# 05_-_Gate_Drivers.net
KiCad netlist of a schematic drawn in Altium Designer
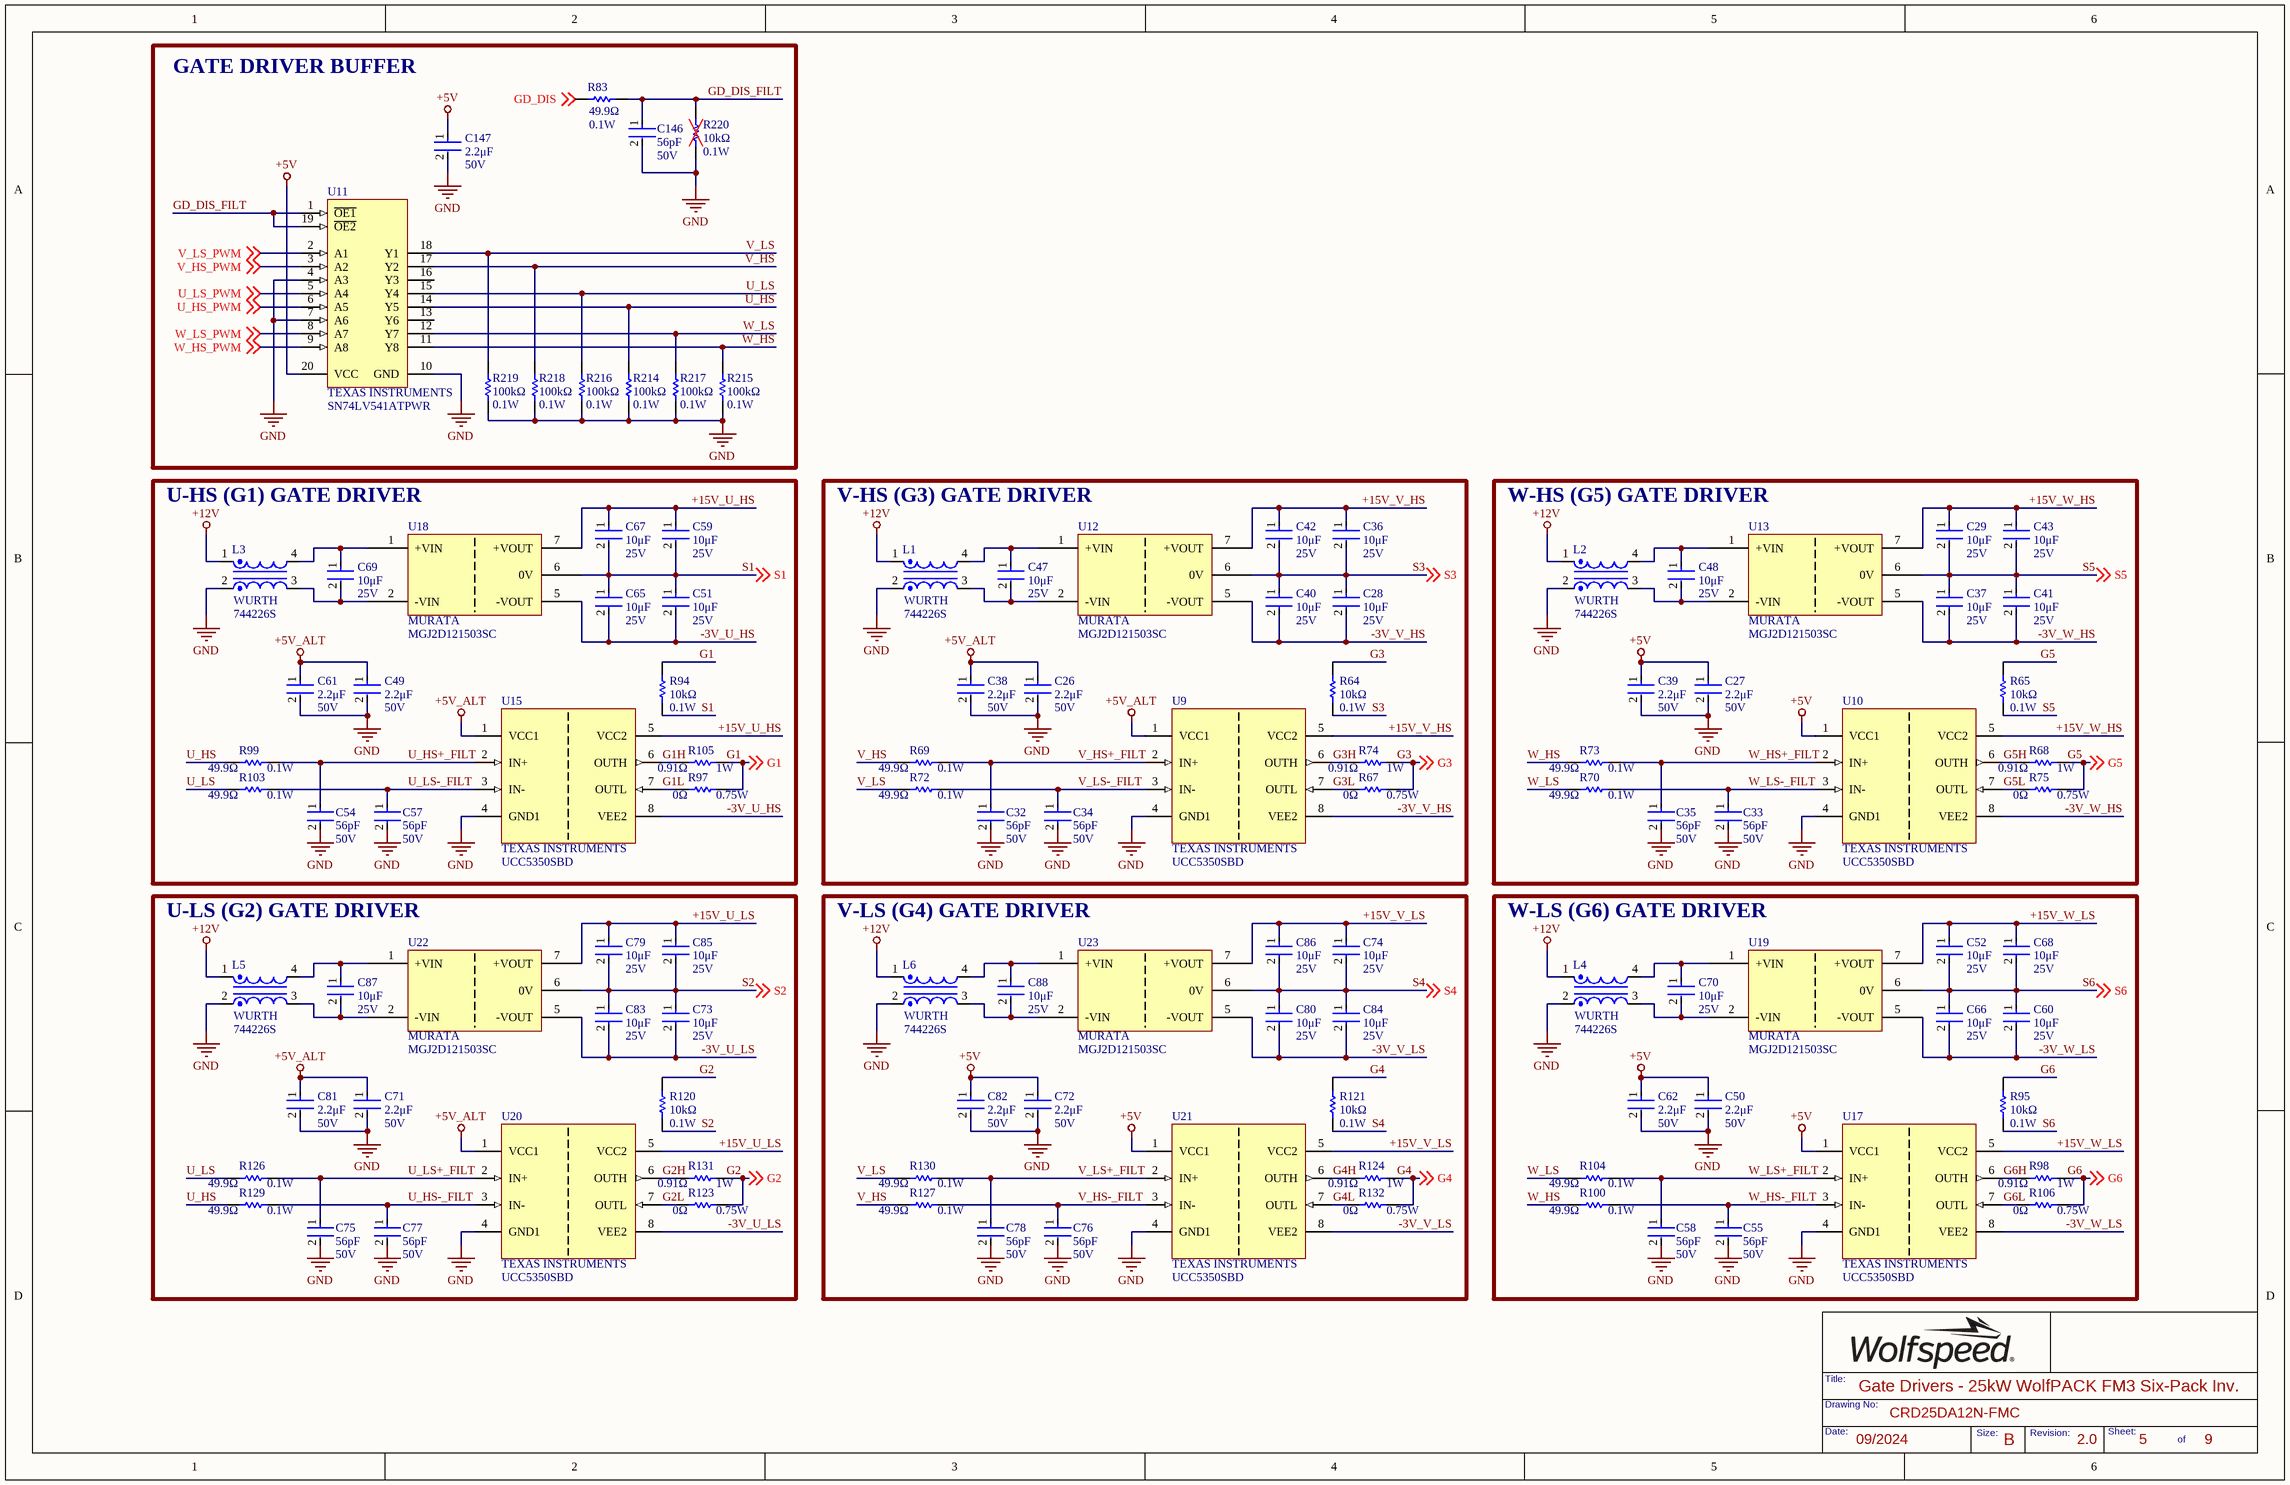
[diagram p0: 05 - Gate Drivers.SchDoc]

(export (version "E")
  (design (tool "Eeschema 10.0.6"))
  (components
    (comp (ref "C26")
      (value "GRT188R61H225ME13D")
      (footprint "FP-C0603C-CF-IPC_B")
      (description "CAP CER 2.2UF 50V X5R 0603")
      (fields
        (field (name "MANUFACTURER") "MURATA")
        (field (name "TOLERANCE") "20%")
        (field (name "VOLTAGE RATING") "50V")
        (field (name "CAPACITANCE") "2.2μF")
      )
      (libsource (lib "Inverter_25kW") (part "GRT188R61H225ME13D"))
    )
    (comp (ref "C27")
      (value "GRT188R61H225ME13D")
      (footprint "FP-C0603C-CF-IPC_B")
      (description "CAP CER 2.2UF 50V X5R 0603")
      (fields
        (field (name "MANUFACTURER") "MURATA")
        (field (name "TOLERANCE") "20%")
        (field (name "VOLTAGE RATING") "50V")
        (field (name "CAPACITANCE") "2.2μF")
      )
      (libsource (lib "Inverter_25kW") (part "GRT188R61H225ME13D"))
    )
    (comp (ref "C28")
      (value "CL31B106KAHSFNE")
      (footprint "FP-CL31-IPC_B")
      (description "CAP CER 10UF 25V X7R 1206")
      (fields
        (field (name "VOLTAGE RATING") "25V")
        (field (name "TOLERANCE") "10%")
        (field (name "CAPACITANCE") "10μF")
        (field (name "MANUFACTURER") "SAMSUNG")
      )
      (libsource (lib "Altium Content Vault") (part "b4654b650e69147ec39a6b967a45e02"))
    )
    (comp (ref "C29")
      (value "CL31B106KAHSFNE")
      (footprint "FP-CL31-IPC_B")
      (description "CAP CER 10UF 25V X7R 1206")
      (fields
        (field (name "VOLTAGE RATING") "25V")
        (field (name "TOLERANCE") "10%")
        (field (name "CAPACITANCE") "10μF")
        (field (name "MANUFACTURER") "SAMSUNG")
      )
      (libsource (lib "Altium Content Vault") (part "b4654b650e69147ec39a6b967a45e02"))
    )
    (comp (ref "C32")
      (value "CL10C560JB8NNNC")
      (footprint "FP-C0603C-CF-IPC_B")
      (description "CAP CER 56PF 50V C0G/NP0 0603")
      (fields
        (field (name "MANUFACTURER") "SAMSUNG")
        (field (name "TOLERANCE") "5%")
        (field (name "CAPACITANCE") "56pF")
        (field (name "VOLTAGE RATING") "50V")
      )
      (libsource (lib "Inverter_25kW") (part "CL10C560JB8NNNC"))
    )
    (comp (ref "C33")
      (value "CL10C560JB8NNNC")
      (footprint "FP-C0603C-CF-IPC_B")
      (description "CAP CER 56PF 50V C0G/NP0 0603")
      (fields
        (field (name "MANUFACTURER") "SAMSUNG")
        (field (name "TOLERANCE") "5%")
        (field (name "CAPACITANCE") "56pF")
        (field (name "VOLTAGE RATING") "50V")
      )
      (libsource (lib "Inverter_25kW") (part "CL10C560JB8NNNC"))
    )
    (comp (ref "C34")
      (value "CL10C560JB8NNNC")
      (footprint "FP-C0603C-CF-IPC_B")
      (description "CAP CER 56PF 50V C0G/NP0 0603")
      (fields
        (field (name "MANUFACTURER") "SAMSUNG")
        (field (name "TOLERANCE") "5%")
        (field (name "CAPACITANCE") "56pF")
        (field (name "VOLTAGE RATING") "50V")
      )
      (libsource (lib "Inverter_25kW") (part "CL10C560JB8NNNC"))
    )
    (comp (ref "C35")
      (value "CL10C560JB8NNNC")
      (footprint "FP-C0603C-CF-IPC_B")
      (description "CAP CER 56PF 50V C0G/NP0 0603")
      (fields
        (field (name "MANUFACTURER") "SAMSUNG")
        (field (name "TOLERANCE") "5%")
        (field (name "CAPACITANCE") "56pF")
        (field (name "VOLTAGE RATING") "50V")
      )
      (libsource (lib "Inverter_25kW") (part "CL10C560JB8NNNC"))
    )
    (comp (ref "C36")
      (value "CL31B106KAHSFNE")
      (footprint "FP-CL31-IPC_B")
      (description "CAP CER 10UF 25V X7R 1206")
      (fields
        (field (name "VOLTAGE RATING") "25V")
        (field (name "TOLERANCE") "10%")
        (field (name "CAPACITANCE") "10μF")
        (field (name "MANUFACTURER") "SAMSUNG")
      )
      (libsource (lib "Altium Content Vault") (part "b4654b650e69147ec39a6b967a45e02"))
    )
    (comp (ref "C37")
      (value "CL31B106KAHSFNE")
      (footprint "FP-CL31-IPC_B")
      (description "CAP CER 10UF 25V X7R 1206")
      (fields
        (field (name "VOLTAGE RATING") "25V")
        (field (name "TOLERANCE") "10%")
        (field (name "CAPACITANCE") "10μF")
        (field (name "MANUFACTURER") "SAMSUNG")
      )
      (libsource (lib "Altium Content Vault") (part "b4654b650e69147ec39a6b967a45e02"))
    )
    (comp (ref "C38")
      (value "GRT188R61H225ME13D")
      (footprint "FP-C0603C-CF-IPC_B")
      (description "CAP CER 2.2UF 50V X5R 0603")
      (fields
        (field (name "MANUFACTURER") "MURATA")
        (field (name "TOLERANCE") "20%")
        (field (name "VOLTAGE RATING") "50V")
        (field (name "CAPACITANCE") "2.2μF")
      )
      (libsource (lib "Inverter_25kW") (part "GRT188R61H225ME13D"))
    )
    (comp (ref "C39")
      (value "GRT188R61H225ME13D")
      (footprint "FP-C0603C-CF-IPC_B")
      (description "CAP CER 2.2UF 50V X5R 0603")
      (fields
        (field (name "MANUFACTURER") "MURATA")
        (field (name "TOLERANCE") "20%")
        (field (name "VOLTAGE RATING") "50V")
        (field (name "CAPACITANCE") "2.2μF")
      )
      (libsource (lib "Inverter_25kW") (part "GRT188R61H225ME13D"))
    )
    (comp (ref "C40")
      (value "CL31B106KAHSFNE")
      (footprint "FP-CL31-IPC_B")
      (description "CAP CER 10UF 25V X7R 1206")
      (fields
        (field (name "VOLTAGE RATING") "25V")
        (field (name "TOLERANCE") "10%")
        (field (name "CAPACITANCE") "10μF")
        (field (name "MANUFACTURER") "SAMSUNG")
      )
      (libsource (lib "Altium Content Vault") (part "b4654b650e69147ec39a6b967a45e02"))
    )
    (comp (ref "C41")
      (value "CL31B106KAHSFNE")
      (footprint "FP-CL31-IPC_B")
      (description "CAP CER 10UF 25V X7R 1206")
      (fields
        (field (name "VOLTAGE RATING") "25V")
        (field (name "TOLERANCE") "10%")
        (field (name "CAPACITANCE") "10μF")
        (field (name "MANUFACTURER") "SAMSUNG")
      )
      (libsource (lib "Altium Content Vault") (part "b4654b650e69147ec39a6b967a45e02"))
    )
    (comp (ref "C42")
      (value "CL31B106KAHSFNE")
      (footprint "FP-CL31-IPC_B")
      (description "CAP CER 10UF 25V X7R 1206")
      (fields
        (field (name "VOLTAGE RATING") "25V")
        (field (name "TOLERANCE") "10%")
        (field (name "CAPACITANCE") "10μF")
        (field (name "MANUFACTURER") "SAMSUNG")
      )
      (libsource (lib "Altium Content Vault") (part "b4654b650e69147ec39a6b967a45e02"))
    )
    (comp (ref "C43")
      (value "CL31B106KAHSFNE")
      (footprint "FP-CL31-IPC_B")
      (description "CAP CER 10UF 25V X7R 1206")
      (fields
        (field (name "VOLTAGE RATING") "25V")
        (field (name "TOLERANCE") "10%")
        (field (name "CAPACITANCE") "10μF")
        (field (name "MANUFACTURER") "SAMSUNG")
      )
      (libsource (lib "Altium Content Vault") (part "b4654b650e69147ec39a6b967a45e02"))
    )
    (comp (ref "C47")
      (value "CL31B106KAHSFNE")
      (footprint "FP-CL31-IPC_B")
      (description "CAP CER 10UF 25V X7R 1206")
      (fields
        (field (name "VOLTAGE RATING") "25V")
        (field (name "TOLERANCE") "10%")
        (field (name "CAPACITANCE") "10μF")
        (field (name "MANUFACTURER") "SAMSUNG")
      )
      (libsource (lib "Altium Content Vault") (part "b4654b650e69147ec39a6b967a45e02"))
    )
    (comp (ref "C48")
      (value "CL31B106KAHSFNE")
      (footprint "FP-CL31-IPC_B")
      (description "CAP CER 10UF 25V X7R 1206")
      (fields
        (field (name "VOLTAGE RATING") "25V")
        (field (name "TOLERANCE") "10%")
        (field (name "CAPACITANCE") "10μF")
        (field (name "MANUFACTURER") "SAMSUNG")
      )
      (libsource (lib "Altium Content Vault") (part "b4654b650e69147ec39a6b967a45e02"))
    )
    (comp (ref "C49")
      (value "GRT188R61H225ME13D")
      (footprint "FP-C0603C-CF-IPC_B")
      (description "CAP CER 2.2UF 50V X5R 0603")
      (fields
        (field (name "MANUFACTURER") "MURATA")
        (field (name "TOLERANCE") "20%")
        (field (name "VOLTAGE RATING") "50V")
        (field (name "CAPACITANCE") "2.2μF")
      )
      (libsource (lib "Inverter_25kW") (part "GRT188R61H225ME13D"))
    )
    (comp (ref "C50")
      (value "GRT188R61H225ME13D")
      (footprint "FP-C0603C-CF-IPC_B")
      (description "CAP CER 2.2UF 50V X5R 0603")
      (fields
        (field (name "MANUFACTURER") "MURATA")
        (field (name "TOLERANCE") "20%")
        (field (name "VOLTAGE RATING") "50V")
        (field (name "CAPACITANCE") "2.2μF")
      )
      (libsource (lib "Inverter_25kW") (part "GRT188R61H225ME13D"))
    )
    (comp (ref "C51")
      (value "CL31B106KAHSFNE")
      (footprint "FP-CL31-IPC_B")
      (description "CAP CER 10UF 25V X7R 1206")
      (fields
        (field (name "VOLTAGE RATING") "25V")
        (field (name "TOLERANCE") "10%")
        (field (name "CAPACITANCE") "10μF")
        (field (name "MANUFACTURER") "SAMSUNG")
      )
      (libsource (lib "Altium Content Vault") (part "b4654b650e69147ec39a6b967a45e02"))
    )
    (comp (ref "C52")
      (value "CL31B106KAHSFNE")
      (footprint "FP-CL31-IPC_B")
      (description "CAP CER 10UF 25V X7R 1206")
      (fields
        (field (name "VOLTAGE RATING") "25V")
        (field (name "TOLERANCE") "10%")
        (field (name "CAPACITANCE") "10μF")
        (field (name "MANUFACTURER") "SAMSUNG")
      )
      (libsource (lib "Altium Content Vault") (part "b4654b650e69147ec39a6b967a45e02"))
    )
    (comp (ref "C54")
      (value "CL10C560JB8NNNC")
      (footprint "FP-C0603C-CF-IPC_B")
      (description "CAP CER 56PF 50V C0G/NP0 0603")
      (fields
        (field (name "MANUFACTURER") "SAMSUNG")
        (field (name "TOLERANCE") "5%")
        (field (name "CAPACITANCE") "56pF")
        (field (name "VOLTAGE RATING") "50V")
      )
      (libsource (lib "Inverter_25kW") (part "CL10C560JB8NNNC"))
    )
    (comp (ref "C55")
      (value "CL10C560JB8NNNC")
      (footprint "FP-C0603C-CF-IPC_B")
      (description "CAP CER 56PF 50V C0G/NP0 0603")
      (fields
        (field (name "MANUFACTURER") "SAMSUNG")
        (field (name "TOLERANCE") "5%")
        (field (name "CAPACITANCE") "56pF")
        (field (name "VOLTAGE RATING") "50V")
      )
      (libsource (lib "Inverter_25kW") (part "CL10C560JB8NNNC"))
    )
    (comp (ref "C57")
      (value "CL10C560JB8NNNC")
      (footprint "FP-C0603C-CF-IPC_B")
      (description "CAP CER 56PF 50V C0G/NP0 0603")
      (fields
        (field (name "MANUFACTURER") "SAMSUNG")
        (field (name "TOLERANCE") "5%")
        (field (name "CAPACITANCE") "56pF")
        (field (name "VOLTAGE RATING") "50V")
      )
      (libsource (lib "Inverter_25kW") (part "CL10C560JB8NNNC"))
    )
    (comp (ref "C58")
      (value "CL10C560JB8NNNC")
      (footprint "FP-C0603C-CF-IPC_B")
      (description "CAP CER 56PF 50V C0G/NP0 0603")
      (fields
        (field (name "MANUFACTURER") "SAMSUNG")
        (field (name "TOLERANCE") "5%")
        (field (name "CAPACITANCE") "56pF")
        (field (name "VOLTAGE RATING") "50V")
      )
      (libsource (lib "Inverter_25kW") (part "CL10C560JB8NNNC"))
    )
    (comp (ref "C59")
      (value "CL31B106KAHSFNE")
      (footprint "FP-CL31-IPC_B")
      (description "CAP CER 10UF 25V X7R 1206")
      (fields
        (field (name "VOLTAGE RATING") "25V")
        (field (name "TOLERANCE") "10%")
        (field (name "CAPACITANCE") "10μF")
        (field (name "MANUFACTURER") "SAMSUNG")
      )
      (libsource (lib "Altium Content Vault") (part "b4654b650e69147ec39a6b967a45e02"))
    )
    (comp (ref "C60")
      (value "CL31B106KAHSFNE")
      (footprint "FP-CL31-IPC_B")
      (description "CAP CER 10UF 25V X7R 1206")
      (fields
        (field (name "VOLTAGE RATING") "25V")
        (field (name "TOLERANCE") "10%")
        (field (name "CAPACITANCE") "10μF")
        (field (name "MANUFACTURER") "SAMSUNG")
      )
      (libsource (lib "Altium Content Vault") (part "b4654b650e69147ec39a6b967a45e02"))
    )
    (comp (ref "C61")
      (value "GRT188R61H225ME13D")
      (footprint "FP-C0603C-CF-IPC_B")
      (description "CAP CER 2.2UF 50V X5R 0603")
      (fields
        (field (name "MANUFACTURER") "MURATA")
        (field (name "TOLERANCE") "20%")
        (field (name "VOLTAGE RATING") "50V")
        (field (name "CAPACITANCE") "2.2μF")
      )
      (libsource (lib "Inverter_25kW") (part "GRT188R61H225ME13D"))
    )
    (comp (ref "C62")
      (value "GRT188R61H225ME13D")
      (footprint "FP-C0603C-CF-IPC_B")
      (description "CAP CER 2.2UF 50V X5R 0603")
      (fields
        (field (name "MANUFACTURER") "MURATA")
        (field (name "TOLERANCE") "20%")
        (field (name "VOLTAGE RATING") "50V")
        (field (name "CAPACITANCE") "2.2μF")
      )
      (libsource (lib "Inverter_25kW") (part "GRT188R61H225ME13D"))
    )
    (comp (ref "C65")
      (value "CL31B106KAHSFNE")
      (footprint "FP-CL31-IPC_B")
      (description "CAP CER 10UF 25V X7R 1206")
      (fields
        (field (name "VOLTAGE RATING") "25V")
        (field (name "TOLERANCE") "10%")
        (field (name "CAPACITANCE") "10μF")
        (field (name "MANUFACTURER") "SAMSUNG")
      )
      (libsource (lib "Altium Content Vault") (part "b4654b650e69147ec39a6b967a45e02"))
    )
    (comp (ref "C66")
      (value "CL31B106KAHSFNE")
      (footprint "FP-CL31-IPC_B")
      (description "CAP CER 10UF 25V X7R 1206")
      (fields
        (field (name "VOLTAGE RATING") "25V")
        (field (name "TOLERANCE") "10%")
        (field (name "CAPACITANCE") "10μF")
        (field (name "MANUFACTURER") "SAMSUNG")
      )
      (libsource (lib "Altium Content Vault") (part "b4654b650e69147ec39a6b967a45e02"))
    )
    (comp (ref "C67")
      (value "CL31B106KAHSFNE")
      (footprint "FP-CL31-IPC_B")
      (description "CAP CER 10UF 25V X7R 1206")
      (fields
        (field (name "VOLTAGE RATING") "25V")
        (field (name "TOLERANCE") "10%")
        (field (name "CAPACITANCE") "10μF")
        (field (name "MANUFACTURER") "SAMSUNG")
      )
      (libsource (lib "Altium Content Vault") (part "b4654b650e69147ec39a6b967a45e02"))
    )
    (comp (ref "C68")
      (value "CL31B106KAHSFNE")
      (footprint "FP-CL31-IPC_B")
      (description "CAP CER 10UF 25V X7R 1206")
      (fields
        (field (name "VOLTAGE RATING") "25V")
        (field (name "TOLERANCE") "10%")
        (field (name "CAPACITANCE") "10μF")
        (field (name "MANUFACTURER") "SAMSUNG")
      )
      (libsource (lib "Altium Content Vault") (part "b4654b650e69147ec39a6b967a45e02"))
    )
    (comp (ref "C69")
      (value "CL31B106KAHSFNE")
      (footprint "FP-CL31-IPC_B")
      (description "CAP CER 10UF 25V X7R 1206")
      (fields
        (field (name "VOLTAGE RATING") "25V")
        (field (name "TOLERANCE") "10%")
        (field (name "CAPACITANCE") "10μF")
        (field (name "MANUFACTURER") "SAMSUNG")
      )
      (libsource (lib "Altium Content Vault") (part "b4654b650e69147ec39a6b967a45e02"))
    )
    (comp (ref "C70")
      (value "CL31B106KAHSFNE")
      (footprint "FP-CL31-IPC_B")
      (description "CAP CER 10UF 25V X7R 1206")
      (fields
        (field (name "VOLTAGE RATING") "25V")
        (field (name "TOLERANCE") "10%")
        (field (name "CAPACITANCE") "10μF")
        (field (name "MANUFACTURER") "SAMSUNG")
      )
      (libsource (lib "Altium Content Vault") (part "b4654b650e69147ec39a6b967a45e02"))
    )
    (comp (ref "C71")
      (value "GRT188R61H225ME13D")
      (footprint "FP-C0603C-CF-IPC_B")
      (description "CAP CER 2.2UF 50V X5R 0603")
      (fields
        (field (name "MANUFACTURER") "MURATA")
        (field (name "TOLERANCE") "20%")
        (field (name "VOLTAGE RATING") "50V")
        (field (name "CAPACITANCE") "2.2μF")
      )
      (libsource (lib "Inverter_25kW") (part "GRT188R61H225ME13D"))
    )
    (comp (ref "C72")
      (value "GRT188R61H225ME13D")
      (footprint "FP-C0603C-CF-IPC_B")
      (description "CAP CER 2.2UF 50V X5R 0603")
      (fields
        (field (name "MANUFACTURER") "MURATA")
        (field (name "TOLERANCE") "20%")
        (field (name "VOLTAGE RATING") "50V")
        (field (name "CAPACITANCE") "2.2μF")
      )
      (libsource (lib "Inverter_25kW") (part "GRT188R61H225ME13D"))
    )
    (comp (ref "C73")
      (value "CL31B106KAHSFNE")
      (footprint "FP-CL31-IPC_B")
      (description "CAP CER 10UF 25V X7R 1206")
      (fields
        (field (name "VOLTAGE RATING") "25V")
        (field (name "TOLERANCE") "10%")
        (field (name "CAPACITANCE") "10μF")
        (field (name "MANUFACTURER") "SAMSUNG")
      )
      (libsource (lib "Altium Content Vault") (part "b4654b650e69147ec39a6b967a45e02"))
    )
    (comp (ref "C74")
      (value "CL31B106KAHSFNE")
      (footprint "FP-CL31-IPC_B")
      (description "CAP CER 10UF 25V X7R 1206")
      (fields
        (field (name "VOLTAGE RATING") "25V")
        (field (name "TOLERANCE") "10%")
        (field (name "CAPACITANCE") "10μF")
        (field (name "MANUFACTURER") "SAMSUNG")
      )
      (libsource (lib "Altium Content Vault") (part "b4654b650e69147ec39a6b967a45e02"))
    )
    (comp (ref "C75")
      (value "CL10C560JB8NNNC")
      (footprint "FP-C0603C-CF-IPC_B")
      (description "CAP CER 56PF 50V C0G/NP0 0603")
      (fields
        (field (name "MANUFACTURER") "SAMSUNG")
        (field (name "TOLERANCE") "5%")
        (field (name "CAPACITANCE") "56pF")
        (field (name "VOLTAGE RATING") "50V")
      )
      (libsource (lib "Inverter_25kW") (part "CL10C560JB8NNNC"))
    )
    (comp (ref "C76")
      (value "CL10C560JB8NNNC")
      (footprint "FP-C0603C-CF-IPC_B")
      (description "CAP CER 56PF 50V C0G/NP0 0603")
      (fields
        (field (name "MANUFACTURER") "SAMSUNG")
        (field (name "TOLERANCE") "5%")
        (field (name "CAPACITANCE") "56pF")
        (field (name "VOLTAGE RATING") "50V")
      )
      (libsource (lib "Inverter_25kW") (part "CL10C560JB8NNNC"))
    )
    (comp (ref "C77")
      (value "CL10C560JB8NNNC")
      (footprint "FP-C0603C-CF-IPC_B")
      (description "CAP CER 56PF 50V C0G/NP0 0603")
      (fields
        (field (name "MANUFACTURER") "SAMSUNG")
        (field (name "TOLERANCE") "5%")
        (field (name "CAPACITANCE") "56pF")
        (field (name "VOLTAGE RATING") "50V")
      )
      (libsource (lib "Inverter_25kW") (part "CL10C560JB8NNNC"))
    )
    (comp (ref "C78")
      (value "CL10C560JB8NNNC")
      (footprint "FP-C0603C-CF-IPC_B")
      (description "CAP CER 56PF 50V C0G/NP0 0603")
      (fields
        (field (name "MANUFACTURER") "SAMSUNG")
        (field (name "TOLERANCE") "5%")
        (field (name "CAPACITANCE") "56pF")
        (field (name "VOLTAGE RATING") "50V")
      )
      (libsource (lib "Inverter_25kW") (part "CL10C560JB8NNNC"))
    )
    (comp (ref "C79")
      (value "CL31B106KAHSFNE")
      (footprint "FP-CL31-IPC_B")
      (description "CAP CER 10UF 25V X7R 1206")
      (fields
        (field (name "VOLTAGE RATING") "25V")
        (field (name "TOLERANCE") "10%")
        (field (name "CAPACITANCE") "10μF")
        (field (name "MANUFACTURER") "SAMSUNG")
      )
      (libsource (lib "Altium Content Vault") (part "b4654b650e69147ec39a6b967a45e02"))
    )
    (comp (ref "C80")
      (value "CL31B106KAHSFNE")
      (footprint "FP-CL31-IPC_B")
      (description "CAP CER 10UF 25V X7R 1206")
      (fields
        (field (name "VOLTAGE RATING") "25V")
        (field (name "TOLERANCE") "10%")
        (field (name "CAPACITANCE") "10μF")
        (field (name "MANUFACTURER") "SAMSUNG")
      )
      (libsource (lib "Altium Content Vault") (part "b4654b650e69147ec39a6b967a45e02"))
    )
    (comp (ref "C81")
      (value "GRT188R61H225ME13D")
      (footprint "FP-C0603C-CF-IPC_B")
      (description "CAP CER 2.2UF 50V X5R 0603")
      (fields
        (field (name "MANUFACTURER") "MURATA")
        (field (name "TOLERANCE") "20%")
        (field (name "VOLTAGE RATING") "50V")
        (field (name "CAPACITANCE") "2.2μF")
      )
      (libsource (lib "Inverter_25kW") (part "GRT188R61H225ME13D"))
    )
    (comp (ref "C82")
      (value "GRT188R61H225ME13D")
      (footprint "FP-C0603C-CF-IPC_B")
      (description "CAP CER 2.2UF 50V X5R 0603")
      (fields
        (field (name "MANUFACTURER") "MURATA")
        (field (name "TOLERANCE") "20%")
        (field (name "VOLTAGE RATING") "50V")
        (field (name "CAPACITANCE") "2.2μF")
      )
      (libsource (lib "Inverter_25kW") (part "GRT188R61H225ME13D"))
    )
    (comp (ref "C83")
      (value "CL31B106KAHSFNE")
      (footprint "FP-CL31-IPC_B")
      (description "CAP CER 10UF 25V X7R 1206")
      (fields
        (field (name "VOLTAGE RATING") "25V")
        (field (name "TOLERANCE") "10%")
        (field (name "CAPACITANCE") "10μF")
        (field (name "MANUFACTURER") "SAMSUNG")
      )
      (libsource (lib "Altium Content Vault") (part "b4654b650e69147ec39a6b967a45e02"))
    )
    (comp (ref "C84")
      (value "CL31B106KAHSFNE")
      (footprint "FP-CL31-IPC_B")
      (description "CAP CER 10UF 25V X7R 1206")
      (fields
        (field (name "VOLTAGE RATING") "25V")
        (field (name "TOLERANCE") "10%")
        (field (name "CAPACITANCE") "10μF")
        (field (name "MANUFACTURER") "SAMSUNG")
      )
      (libsource (lib "Altium Content Vault") (part "b4654b650e69147ec39a6b967a45e02"))
    )
    (comp (ref "C85")
      (value "CL31B106KAHSFNE")
      (footprint "FP-CL31-IPC_B")
      (description "CAP CER 10UF 25V X7R 1206")
      (fields
        (field (name "VOLTAGE RATING") "25V")
        (field (name "TOLERANCE") "10%")
        (field (name "CAPACITANCE") "10μF")
        (field (name "MANUFACTURER") "SAMSUNG")
      )
      (libsource (lib "Altium Content Vault") (part "b4654b650e69147ec39a6b967a45e02"))
    )
    (comp (ref "C86")
      (value "CL31B106KAHSFNE")
      (footprint "FP-CL31-IPC_B")
      (description "CAP CER 10UF 25V X7R 1206")
      (fields
        (field (name "VOLTAGE RATING") "25V")
        (field (name "TOLERANCE") "10%")
        (field (name "CAPACITANCE") "10μF")
        (field (name "MANUFACTURER") "SAMSUNG")
      )
      (libsource (lib "Altium Content Vault") (part "b4654b650e69147ec39a6b967a45e02"))
    )
    (comp (ref "C87")
      (value "CL31B106KAHSFNE")
      (footprint "FP-CL31-IPC_B")
      (description "CAP CER 10UF 25V X7R 1206")
      (fields
        (field (name "VOLTAGE RATING") "25V")
        (field (name "TOLERANCE") "10%")
        (field (name "CAPACITANCE") "10μF")
        (field (name "MANUFACTURER") "SAMSUNG")
      )
      (libsource (lib "Altium Content Vault") (part "b4654b650e69147ec39a6b967a45e02"))
    )
    (comp (ref "C88")
      (value "CL31B106KAHSFNE")
      (footprint "FP-CL31-IPC_B")
      (description "CAP CER 10UF 25V X7R 1206")
      (fields
        (field (name "VOLTAGE RATING") "25V")
        (field (name "TOLERANCE") "10%")
        (field (name "CAPACITANCE") "10μF")
        (field (name "MANUFACTURER") "SAMSUNG")
      )
      (libsource (lib "Altium Content Vault") (part "b4654b650e69147ec39a6b967a45e02"))
    )
    (comp (ref "C146")
      (value "CL10C560JB8NNNC")
      (footprint "FP-C0603C-CF-IPC_B")
      (description "CAP CER 56PF 50V C0G/NP0 0603")
      (fields
        (field (name "MANUFACTURER") "SAMSUNG")
        (field (name "TOLERANCE") "5%")
        (field (name "CAPACITANCE") "56pF")
        (field (name "VOLTAGE RATING") "50V")
      )
      (libsource (lib "Inverter_25kW") (part "CL10C560JB8NNNC"))
    )
    (comp (ref "C147")
      (value "GRT188R61H225ME13D")
      (footprint "FP-C0603C-CF-IPC_B")
      (description "CAP CER 2.2UF 50V X5R 0603")
      (fields
        (field (name "MANUFACTURER") "MURATA")
        (field (name "TOLERANCE") "20%")
        (field (name "VOLTAGE RATING") "50V")
        (field (name "CAPACITANCE") "2.2μF")
      )
      (libsource (lib "Inverter_25kW") (part "GRT188R61H225ME13D"))
    )
    (comp (ref "L1")
      (value "744226S")
      (footprint "Inverter_25kW:WE-SL2")
      (description "CMC 10UH 1.6A 2LN 920 OHM SMD")
      (fields
        (field (name "MANUFACTURER") "WURTH ELECTRONIK")
        (field (name "TOLERANCE") "30%")
        (field (name "MANUFACTURER PRINT") "WURTH")
      )
      (libsource (lib "Inverter_25kW") (part "744226S"))
    )
    (comp (ref "L2")
      (value "744226S")
      (footprint "Inverter_25kW:WE-SL2")
      (description "CMC 10UH 1.6A 2LN 920 OHM SMD")
      (fields
        (field (name "MANUFACTURER") "WURTH ELECTRONIK")
        (field (name "TOLERANCE") "30%")
        (field (name "MANUFACTURER PRINT") "WURTH")
      )
      (libsource (lib "Inverter_25kW") (part "744226S"))
    )
    (comp (ref "L3")
      (value "744226S")
      (footprint "Inverter_25kW:WE-SL2")
      (description "CMC 10UH 1.6A 2LN 920 OHM SMD")
      (fields
        (field (name "MANUFACTURER") "WURTH ELECTRONIK")
        (field (name "TOLERANCE") "30%")
        (field (name "MANUFACTURER PRINT") "WURTH")
      )
      (libsource (lib "Inverter_25kW") (part "744226S"))
    )
    (comp (ref "L4")
      (value "744226S")
      (footprint "Inverter_25kW:WE-SL2")
      (description "CMC 10UH 1.6A 2LN 920 OHM SMD")
      (fields
        (field (name "MANUFACTURER") "WURTH ELECTRONIK")
        (field (name "TOLERANCE") "30%")
        (field (name "MANUFACTURER PRINT") "WURTH")
      )
      (libsource (lib "Inverter_25kW") (part "744226S"))
    )
    (comp (ref "L5")
      (value "744226S")
      (footprint "Inverter_25kW:WE-SL2")
      (description "CMC 10UH 1.6A 2LN 920 OHM SMD")
      (fields
        (field (name "MANUFACTURER") "WURTH ELECTRONIK")
        (field (name "TOLERANCE") "30%")
        (field (name "MANUFACTURER PRINT") "WURTH")
      )
      (libsource (lib "Inverter_25kW") (part "744226S"))
    )
    (comp (ref "L6")
      (value "744226S")
      (footprint "Inverter_25kW:WE-SL2")
      (description "CMC 10UH 1.6A 2LN 920 OHM SMD")
      (fields
        (field (name "MANUFACTURER") "WURTH ELECTRONIK")
        (field (name "TOLERANCE") "30%")
        (field (name "MANUFACTURER PRINT") "WURTH")
      )
      (libsource (lib "Inverter_25kW") (part "744226S"))
    )
    (comp (ref "R64")
      (value "ERJ3EKF1002V")
      (footprint "FP-MCR03-IPC_B")
      (description "RES SMD 10K OHM 1% 1/10W 0603")
      (fields
        (field (name "MANUFACTURER") "PANASONIC")
        (field (name "MANUFACTURER PART NUMBER") "ERJ-3EKF1002V")
        (field (name "RESISTANCE") "10kΩ")
        (field (name "MAX POWER DISSIPATION") "0.1W")
      )
      (libsource (lib "Inverter_25kW") (part "ERJ3EKF1002V"))
    )
    (comp (ref "R65")
      (value "ERJ3EKF1002V")
      (footprint "FP-MCR03-IPC_B")
      (description "RES SMD 10K OHM 1% 1/10W 0603")
      (fields
        (field (name "MANUFACTURER") "PANASONIC")
        (field (name "MANUFACTURER PART NUMBER") "ERJ-3EKF1002V")
        (field (name "RESISTANCE") "10kΩ")
        (field (name "MAX POWER DISSIPATION") "0.1W")
      )
      (libsource (lib "Inverter_25kW") (part "ERJ3EKF1002V"))
    )
    (comp (ref "R67")
      (value "0Ω")
      (footprint "RESC3125X70X40NL20T20")
      (description "RES SMD 0 OHM JUMPER 3/4W 1210")
      (fields
        (field (name "MANUFACTURER") "VISHAY DALE")
        (field (name "MANUFACTURER PART NUMBER") "CRCW12100000Z0EAHP")
        (field (name "POWER RATING") "0.75W")
      )
      (libsource (lib "CRD25DA12N-FMC") (part "CRCW12100000Z0EAHP"))
    )
    (comp (ref "R68")
      (value "0.91Ω")
      (footprint "RESC3125X70X40NL20T20")
      (description "RES 0.91 OHM 1% 1W 1210")
      (fields
        (field (name "MANUFACTURER") "VISHAY DALE")
        (field (name "PART NUMBER") "RCWE1210R910FKEA")
        (field (name "POWER") "1W")
      )
      (libsource (lib "Altium Content Vault") (part "RES"))
    )
    (comp (ref "R69")
      (value "ERJ-3EKF49R9V")
      (footprint "FP-MCR03-IPC_B")
      (description "RES SMD 49.9 OHM 1% 1/10W 0603")
      (fields
        (field (name "MANUFACTURER") "PANASONIC")
        (field (name "TOLERANCE") "1%")
        (field (name "RESISTANCE") "49.9Ω")
        (field (name "POWER RATING") "0.1W")
      )
      (libsource (lib "Inverter_25kW") (part "ERJ-3EKF49R9V"))
    )
    (comp (ref "R70")
      (value "ERJ-3EKF49R9V")
      (footprint "FP-MCR03-IPC_B")
      (description "RES SMD 49.9 OHM 1% 1/10W 0603")
      (fields
        (field (name "MANUFACTURER") "PANASONIC")
        (field (name "TOLERANCE") "1%")
        (field (name "RESISTANCE") "49.9Ω")
        (field (name "POWER RATING") "0.1W")
      )
      (libsource (lib "Inverter_25kW") (part "ERJ-3EKF49R9V"))
    )
    (comp (ref "R72")
      (value "ERJ-3EKF49R9V")
      (footprint "FP-MCR03-IPC_B")
      (description "RES SMD 49.9 OHM 1% 1/10W 0603")
      (fields
        (field (name "MANUFACTURER") "PANASONIC")
        (field (name "TOLERANCE") "1%")
        (field (name "RESISTANCE") "49.9Ω")
        (field (name "POWER RATING") "0.1W")
      )
      (libsource (lib "Inverter_25kW") (part "ERJ-3EKF49R9V"))
    )
    (comp (ref "R73")
      (value "ERJ-3EKF49R9V")
      (footprint "FP-MCR03-IPC_B")
      (description "RES SMD 49.9 OHM 1% 1/10W 0603")
      (fields
        (field (name "MANUFACTURER") "PANASONIC")
        (field (name "TOLERANCE") "1%")
        (field (name "RESISTANCE") "49.9Ω")
        (field (name "POWER RATING") "0.1W")
      )
      (libsource (lib "Inverter_25kW") (part "ERJ-3EKF49R9V"))
    )
    (comp (ref "R74")
      (value "0.91Ω")
      (footprint "RESC3125X70X40NL20T20")
      (description "RES 0.91 OHM 1% 1W 1210")
      (fields
        (field (name "MANUFACTURER") "VISHAY DALE")
        (field (name "PART NUMBER") "RCWE1210R910FKEA")
        (field (name "POWER") "1W")
      )
      (libsource (lib "Altium Content Vault") (part "RES"))
    )
    (comp (ref "R75")
      (value "0Ω")
      (footprint "RESC3125X70X40NL20T20")
      (description "RES SMD 0 OHM JUMPER 3/4W 1210")
      (fields
        (field (name "MANUFACTURER") "VISHAY DALE")
        (field (name "MANUFACTURER PART NUMBER") "CRCW12100000Z0EAHP")
        (field (name "POWER RATING") "0.75W")
      )
      (libsource (lib "CRD25DA12N-FMC") (part "CRCW12100000Z0EAHP"))
    )
    (comp (ref "R83")
      (value "ERJ-3EKF49R9V")
      (footprint "FP-MCR03-IPC_B")
      (description "RES SMD 49.9 OHM 1% 1/10W 0603")
      (fields
        (field (name "MANUFACTURER") "PANASONIC")
        (field (name "TOLERANCE") "1%")
        (field (name "RESISTANCE") "49.9Ω")
        (field (name "POWER RATING") "0.1W")
      )
      (libsource (lib "Inverter_25kW") (part "ERJ-3EKF49R9V"))
    )
    (comp (ref "R94")
      (value "ERJ3EKF1002V")
      (footprint "FP-MCR03-IPC_B")
      (description "RES SMD 10K OHM 1% 1/10W 0603")
      (fields
        (field (name "MANUFACTURER") "PANASONIC")
        (field (name "MANUFACTURER PART NUMBER") "ERJ-3EKF1002V")
        (field (name "RESISTANCE") "10kΩ")
        (field (name "MAX POWER DISSIPATION") "0.1W")
      )
      (libsource (lib "Inverter_25kW") (part "ERJ3EKF1002V"))
    )
    (comp (ref "R95")
      (value "ERJ3EKF1002V")
      (footprint "FP-MCR03-IPC_B")
      (description "RES SMD 10K OHM 1% 1/10W 0603")
      (fields
        (field (name "MANUFACTURER") "PANASONIC")
        (field (name "MANUFACTURER PART NUMBER") "ERJ-3EKF1002V")
        (field (name "RESISTANCE") "10kΩ")
        (field (name "MAX POWER DISSIPATION") "0.1W")
      )
      (libsource (lib "Inverter_25kW") (part "ERJ3EKF1002V"))
    )
    (comp (ref "R97")
      (value "0Ω")
      (footprint "RESC3125X70X40NL20T20")
      (description "RES SMD 0 OHM JUMPER 3/4W 1210")
      (fields
        (field (name "MANUFACTURER") "VISHAY DALE")
        (field (name "MANUFACTURER PART NUMBER") "CRCW12100000Z0EAHP")
        (field (name "POWER RATING") "0.75W")
      )
      (libsource (lib "CRD25DA12N-FMC") (part "CRCW12100000Z0EAHP"))
    )
    (comp (ref "R98")
      (value "0.91Ω")
      (footprint "RESC3125X70X40NL20T20")
      (description "RES 0.91 OHM 1% 1W 1210")
      (fields
        (field (name "MANUFACTURER") "VISHAY DALE")
        (field (name "PART NUMBER") "RCWE1210R910FKEA")
        (field (name "POWER") "1W")
      )
      (libsource (lib "Altium Content Vault") (part "RES"))
    )
    (comp (ref "R99")
      (value "ERJ-3EKF49R9V")
      (footprint "FP-MCR03-IPC_B")
      (description "RES SMD 49.9 OHM 1% 1/10W 0603")
      (fields
        (field (name "MANUFACTURER") "PANASONIC")
        (field (name "TOLERANCE") "1%")
        (field (name "RESISTANCE") "49.9Ω")
        (field (name "POWER RATING") "0.1W")
      )
      (libsource (lib "Inverter_25kW") (part "ERJ-3EKF49R9V"))
    )
    (comp (ref "R100")
      (value "ERJ-3EKF49R9V")
      (footprint "FP-MCR03-IPC_B")
      (description "RES SMD 49.9 OHM 1% 1/10W 0603")
      (fields
        (field (name "MANUFACTURER") "PANASONIC")
        (field (name "TOLERANCE") "1%")
        (field (name "RESISTANCE") "49.9Ω")
        (field (name "POWER RATING") "0.1W")
      )
      (libsource (lib "Inverter_25kW") (part "ERJ-3EKF49R9V"))
    )
    (comp (ref "R103")
      (value "ERJ-3EKF49R9V")
      (footprint "FP-MCR03-IPC_B")
      (description "RES SMD 49.9 OHM 1% 1/10W 0603")
      (fields
        (field (name "MANUFACTURER") "PANASONIC")
        (field (name "TOLERANCE") "1%")
        (field (name "RESISTANCE") "49.9Ω")
        (field (name "POWER RATING") "0.1W")
      )
      (libsource (lib "Inverter_25kW") (part "ERJ-3EKF49R9V"))
    )
    (comp (ref "R104")
      (value "ERJ-3EKF49R9V")
      (footprint "FP-MCR03-IPC_B")
      (description "RES SMD 49.9 OHM 1% 1/10W 0603")
      (fields
        (field (name "MANUFACTURER") "PANASONIC")
        (field (name "TOLERANCE") "1%")
        (field (name "RESISTANCE") "49.9Ω")
        (field (name "POWER RATING") "0.1W")
      )
      (libsource (lib "Inverter_25kW") (part "ERJ-3EKF49R9V"))
    )
    (comp (ref "R105")
      (value "0.91Ω")
      (footprint "RESC3125X70X40NL20T20")
      (description "RES 0.91 OHM 1% 1W 1210")
      (fields
        (field (name "MANUFACTURER") "VISHAY DALE")
        (field (name "PART NUMBER") "RCWE1210R910FKEA")
        (field (name "POWER") "1W")
      )
      (libsource (lib "Altium Content Vault") (part "RES"))
    )
    (comp (ref "R106")
      (value "0Ω")
      (footprint "RESC3125X70X40NL20T20")
      (description "RES SMD 0 OHM JUMPER 3/4W 1210")
      (fields
        (field (name "MANUFACTURER") "VISHAY DALE")
        (field (name "MANUFACTURER PART NUMBER") "CRCW12100000Z0EAHP")
        (field (name "POWER RATING") "0.75W")
      )
      (libsource (lib "CRD25DA12N-FMC") (part "CRCW12100000Z0EAHP"))
    )
    (comp (ref "R120")
      (value "ERJ3EKF1002V")
      (footprint "FP-MCR03-IPC_B")
      (description "RES SMD 10K OHM 1% 1/10W 0603")
      (fields
        (field (name "MANUFACTURER") "PANASONIC")
        (field (name "MANUFACTURER PART NUMBER") "ERJ-3EKF1002V")
        (field (name "RESISTANCE") "10kΩ")
        (field (name "MAX POWER DISSIPATION") "0.1W")
      )
      (libsource (lib "Inverter_25kW") (part "ERJ3EKF1002V"))
    )
    (comp (ref "R121")
      (value "ERJ3EKF1002V")
      (footprint "FP-MCR03-IPC_B")
      (description "RES SMD 10K OHM 1% 1/10W 0603")
      (fields
        (field (name "MANUFACTURER") "PANASONIC")
        (field (name "MANUFACTURER PART NUMBER") "ERJ-3EKF1002V")
        (field (name "RESISTANCE") "10kΩ")
        (field (name "MAX POWER DISSIPATION") "0.1W")
      )
      (libsource (lib "Inverter_25kW") (part "ERJ3EKF1002V"))
    )
    (comp (ref "R123")
      (value "0Ω")
      (footprint "RESC3125X70X40NL20T20")
      (description "RES SMD 0 OHM JUMPER 3/4W 1210")
      (fields
        (field (name "MANUFACTURER") "VISHAY DALE")
        (field (name "MANUFACTURER PART NUMBER") "CRCW12100000Z0EAHP")
        (field (name "POWER RATING") "0.75W")
      )
      (libsource (lib "CRD25DA12N-FMC") (part "CRCW12100000Z0EAHP"))
    )
    (comp (ref "R124")
      (value "0.91Ω")
      (footprint "RESC3125X70X40NL20T20")
      (description "RES 0.91 OHM 1% 1W 1210")
      (fields
        (field (name "MANUFACTURER") "VISHAY DALE")
        (field (name "PART NUMBER") "RCWE1210R910FKEA")
        (field (name "POWER") "1W")
      )
      (libsource (lib "Altium Content Vault") (part "RES"))
    )
    (comp (ref "R126")
      (value "ERJ-3EKF49R9V")
      (footprint "FP-MCR03-IPC_B")
      (description "RES SMD 49.9 OHM 1% 1/10W 0603")
      (fields
        (field (name "MANUFACTURER") "PANASONIC")
        (field (name "TOLERANCE") "1%")
        (field (name "RESISTANCE") "49.9Ω")
        (field (name "POWER RATING") "0.1W")
      )
      (libsource (lib "Inverter_25kW") (part "ERJ-3EKF49R9V"))
    )
    (comp (ref "R127")
      (value "ERJ-3EKF49R9V")
      (footprint "FP-MCR03-IPC_B")
      (description "RES SMD 49.9 OHM 1% 1/10W 0603")
      (fields
        (field (name "MANUFACTURER") "PANASONIC")
        (field (name "TOLERANCE") "1%")
        (field (name "RESISTANCE") "49.9Ω")
        (field (name "POWER RATING") "0.1W")
      )
      (libsource (lib "Inverter_25kW") (part "ERJ-3EKF49R9V"))
    )
    (comp (ref "R129")
      (value "ERJ-3EKF49R9V")
      (footprint "FP-MCR03-IPC_B")
      (description "RES SMD 49.9 OHM 1% 1/10W 0603")
      (fields
        (field (name "MANUFACTURER") "PANASONIC")
        (field (name "TOLERANCE") "1%")
        (field (name "RESISTANCE") "49.9Ω")
        (field (name "POWER RATING") "0.1W")
      )
      (libsource (lib "Inverter_25kW") (part "ERJ-3EKF49R9V"))
    )
    (comp (ref "R130")
      (value "ERJ-3EKF49R9V")
      (footprint "FP-MCR03-IPC_B")
      (description "RES SMD 49.9 OHM 1% 1/10W 0603")
      (fields
        (field (name "MANUFACTURER") "PANASONIC")
        (field (name "TOLERANCE") "1%")
        (field (name "RESISTANCE") "49.9Ω")
        (field (name "POWER RATING") "0.1W")
      )
      (libsource (lib "Inverter_25kW") (part "ERJ-3EKF49R9V"))
    )
    (comp (ref "R131")
      (value "0.91Ω")
      (footprint "RESC3125X70X40NL20T20")
      (description "RES 0.91 OHM 1% 1W 1210")
      (fields
        (field (name "MANUFACTURER") "VISHAY DALE")
        (field (name "PART NUMBER") "RCWE1210R910FKEA")
        (field (name "POWER") "1W")
      )
      (libsource (lib "Altium Content Vault") (part "RES"))
    )
    (comp (ref "R132")
      (value "0Ω")
      (footprint "RESC3125X70X40NL20T20")
      (description "RES SMD 0 OHM JUMPER 3/4W 1210")
      (fields
        (field (name "MANUFACTURER") "VISHAY DALE")
        (field (name "MANUFACTURER PART NUMBER") "CRCW12100000Z0EAHP")
        (field (name "POWER RATING") "0.75W")
      )
      (libsource (lib "CRD25DA12N-FMC") (part "CRCW12100000Z0EAHP"))
    )
    (comp (ref "R214")
      (value "RC0603FR-07100KL")
      (footprint "FP-MCR03-IPC_B")
      (description "RES 100K OHM 1% 1/10W 0603")
      (fields
        (field (name "MANUFACTURER") "YAGEO")
        (field (name "TOLERANCE") "1%")
        (field (name "RESISTANCE") "100kΩ")
        (field (name "POWER RATING") "0.1W")
      )
      (libsource (lib "Inverter_25kW") (part "RC0603FR-07100KL"))
    )
    (comp (ref "R215")
      (value "RC0603FR-07100KL")
      (footprint "FP-MCR03-IPC_B")
      (description "RES 100K OHM 1% 1/10W 0603")
      (fields
        (field (name "MANUFACTURER") "YAGEO")
        (field (name "TOLERANCE") "1%")
        (field (name "RESISTANCE") "100kΩ")
        (field (name "POWER RATING") "0.1W")
      )
      (libsource (lib "Inverter_25kW") (part "RC0603FR-07100KL"))
    )
    (comp (ref "R216")
      (value "RC0603FR-07100KL")
      (footprint "FP-MCR03-IPC_B")
      (description "RES 100K OHM 1% 1/10W 0603")
      (fields
        (field (name "MANUFACTURER") "YAGEO")
        (field (name "TOLERANCE") "1%")
        (field (name "RESISTANCE") "100kΩ")
        (field (name "POWER RATING") "0.1W")
      )
      (libsource (lib "Inverter_25kW") (part "RC0603FR-07100KL"))
    )
    (comp (ref "R217")
      (value "RC0603FR-07100KL")
      (footprint "FP-MCR03-IPC_B")
      (description "RES 100K OHM 1% 1/10W 0603")
      (fields
        (field (name "MANUFACTURER") "YAGEO")
        (field (name "TOLERANCE") "1%")
        (field (name "RESISTANCE") "100kΩ")
        (field (name "POWER RATING") "0.1W")
      )
      (libsource (lib "Inverter_25kW") (part "RC0603FR-07100KL"))
    )
    (comp (ref "R218")
      (value "RC0603FR-07100KL")
      (footprint "FP-MCR03-IPC_B")
      (description "RES 100K OHM 1% 1/10W 0603")
      (fields
        (field (name "MANUFACTURER") "YAGEO")
        (field (name "TOLERANCE") "1%")
        (field (name "RESISTANCE") "100kΩ")
        (field (name "POWER RATING") "0.1W")
      )
      (libsource (lib "Inverter_25kW") (part "RC0603FR-07100KL"))
    )
    (comp (ref "R219")
      (value "RC0603FR-07100KL")
      (footprint "FP-MCR03-IPC_B")
      (description "RES 100K OHM 1% 1/10W 0603")
      (fields
        (field (name "MANUFACTURER") "YAGEO")
        (field (name "TOLERANCE") "1%")
        (field (name "RESISTANCE") "100kΩ")
        (field (name "POWER RATING") "0.1W")
      )
      (libsource (lib "Inverter_25kW") (part "RC0603FR-07100KL"))
    )
    (comp (ref "R220")
      (value "ERJ3EKF1002V")
      (footprint "FP-MCR03-IPC_B")
      (description "RES SMD 10K OHM 1% 1/10W 0603")
      (fields
        (field (name "MANUFACTURER") "PANASONIC")
        (field (name "MANUFACTURER PART NUMBER") "ERJ-3EKF1002V")
        (field (name "RESISTANCE") "10kΩ")
        (field (name "MAX POWER DISSIPATION") "0.1W")
      )
      (libsource (lib "Inverter_25kW") (part "ERJ3EKF1002V"))
    )
    (comp (ref "U9")
      (value "UCC5350SBD")
      (footprint "D0008B_HV")
      (description "5A/5A, 3-KVRMS SINGLE-CHANNEL IS")
      (fields
        (field (name "MANUFACTURER") "TEXAS INSTRUMENTS")
        (field (name "MANUFACTURER PRINT") "TEXAS INSTRUMENTS")
        (field (name "COPYRIGHT") "Copyright (C) 2021 Ultra Librarian. All rights reserved.")
      )
      (libsource (lib "Inverter_25kW") (part "UCC5350SBD"))
    )
    (comp (ref "U10")
      (value "UCC5350SBD")
      (footprint "D0008B_HV")
      (description "5A/5A, 3-KVRMS SINGLE-CHANNEL IS")
      (fields
        (field (name "MANUFACTURER") "TEXAS INSTRUMENTS")
        (field (name "MANUFACTURER PRINT") "TEXAS INSTRUMENTS")
        (field (name "COPYRIGHT") "Copyright (C) 2021 Ultra Librarian. All rights reserved.")
      )
      (libsource (lib "Inverter_25kW") (part "UCC5350SBD"))
    )
    (comp (ref "U11")
      (value "SN74LV541ATPWR")
      (footprint "PW0020A_L")
      (description "IC BUF NON-INVERT 5.5V 20TSSOP")
      (fields
        (field (name "GENERIC PART NUMBER") "SN74LV541AT")
        (field (name "MANUFACTURER") "TEXAS INSTRUMENTS")
        (field (name "MANUFACTURER PART NUMBER") "SN74LV541ATPWR")
      )
      (libsource (lib "Altium Content Vault") (part "TI-SN54_74_CD74XXXX541XX-20"))
    )
    (comp (ref "U12")
      (value "MGJ2D121503SC")
      (footprint "Inverter_25kW:MGJ2D121509SC")
      (description "DC DC CONVERTER 15V -3V 1.7W")
      (fields (field (name "MANUFACTURER") "MURATA") (field (name "MANUFACTURER PRINT") "MURATA"))
      (libsource (lib "Inverter_25kW") (part "MGJ2D121503SC"))
    )
    (comp (ref "U13")
      (value "MGJ2D121503SC")
      (footprint "Inverter_25kW:MGJ2D121509SC")
      (description "DC DC CONVERTER 15V -3V 1.7W")
      (fields (field (name "MANUFACTURER") "MURATA") (field (name "MANUFACTURER PRINT") "MURATA"))
      (libsource (lib "Inverter_25kW") (part "MGJ2D121503SC"))
    )
    (comp (ref "U15")
      (value "UCC5350SBD")
      (footprint "D0008B_HV")
      (description "5A/5A, 3-KVRMS SINGLE-CHANNEL IS")
      (fields
        (field (name "MANUFACTURER") "TEXAS INSTRUMENTS")
        (field (name "MANUFACTURER PRINT") "TEXAS INSTRUMENTS")
        (field (name "COPYRIGHT") "Copyright (C) 2021 Ultra Librarian. All rights reserved.")
      )
      (libsource (lib "Inverter_25kW") (part "UCC5350SBD"))
    )
    (comp (ref "U17")
      (value "UCC5350SBD")
      (footprint "D0008B_HV")
      (description "5A/5A, 3-KVRMS SINGLE-CHANNEL IS")
      (fields
        (field (name "MANUFACTURER") "TEXAS INSTRUMENTS")
        (field (name "MANUFACTURER PRINT") "TEXAS INSTRUMENTS")
        (field (name "COPYRIGHT") "Copyright (C) 2021 Ultra Librarian. All rights reserved.")
      )
      (libsource (lib "Inverter_25kW") (part "UCC5350SBD"))
    )
    (comp (ref "U18")
      (value "MGJ2D121503SC")
      (footprint "Inverter_25kW:MGJ2D121509SC")
      (description "DC DC CONVERTER 15V -3V 1.7W")
      (fields (field (name "MANUFACTURER") "MURATA") (field (name "MANUFACTURER PRINT") "MURATA"))
      (libsource (lib "Inverter_25kW") (part "MGJ2D121503SC"))
    )
    (comp (ref "U19")
      (value "MGJ2D121503SC")
      (footprint "Inverter_25kW:MGJ2D121509SC")
      (description "DC DC CONVERTER 15V -3V 1.7W")
      (fields (field (name "MANUFACTURER") "MURATA") (field (name "MANUFACTURER PRINT") "MURATA"))
      (libsource (lib "Inverter_25kW") (part "MGJ2D121503SC"))
    )
    (comp (ref "U20")
      (value "UCC5350SBD")
      (footprint "D0008B_HV")
      (description "5A/5A, 3-KVRMS SINGLE-CHANNEL IS")
      (fields
        (field (name "MANUFACTURER") "TEXAS INSTRUMENTS")
        (field (name "MANUFACTURER PRINT") "TEXAS INSTRUMENTS")
        (field (name "COPYRIGHT") "Copyright (C) 2021 Ultra Librarian. All rights reserved.")
      )
      (libsource (lib "Inverter_25kW") (part "UCC5350SBD"))
    )
    (comp (ref "U21")
      (value "UCC5350SBD")
      (footprint "D0008B_HV")
      (description "5A/5A, 3-KVRMS SINGLE-CHANNEL IS")
      (fields
        (field (name "MANUFACTURER") "TEXAS INSTRUMENTS")
        (field (name "MANUFACTURER PRINT") "TEXAS INSTRUMENTS")
        (field (name "COPYRIGHT") "Copyright (C) 2021 Ultra Librarian. All rights reserved.")
      )
      (libsource (lib "Inverter_25kW") (part "UCC5350SBD"))
    )
    (comp (ref "U22")
      (value "MGJ2D121503SC")
      (footprint "Inverter_25kW:MGJ2D121509SC")
      (description "DC DC CONVERTER 15V -3V 1.7W")
      (fields (field (name "MANUFACTURER") "MURATA") (field (name "MANUFACTURER PRINT") "MURATA"))
      (libsource (lib "Inverter_25kW") (part "MGJ2D121503SC"))
    )
    (comp (ref "U23")
      (value "MGJ2D121503SC")
      (footprint "Inverter_25kW:MGJ2D121509SC")
      (description "DC DC CONVERTER 15V -3V 1.7W")
      (fields (field (name "MANUFACTURER") "MURATA") (field (name "MANUFACTURER PRINT") "MURATA"))
      (libsource (lib "Inverter_25kW") (part "MGJ2D121503SC"))
    )
  )
  (nets
    (net (code "1") (name "+5V") (class "Default")
      (node (ref "C147") (pin "1") (pinfunction "1_1") (pintype "passive"))
      (node (ref "C27") (pin "1") (pinfunction "1_1") (pintype "passive"))
      (node (ref "C39") (pin "1") (pinfunction "1_1") (pintype "passive"))
      (node (ref "C50") (pin "1") (pinfunction "1_1") (pintype "passive"))
      (node (ref "C62") (pin "1") (pinfunction "1_1") (pintype "passive"))
      (node (ref "C72") (pin "1") (pinfunction "1_1") (pintype "passive"))
      (node (ref "C82") (pin "1") (pinfunction "1_1") (pintype "passive"))
      (node (ref "U10") (pin "1") (pinfunction "VCC1_1") (pintype "power_in"))
      (node (ref "U11") (pin "20") (pinfunction "VCC_20") (pintype "power_in"))
      (node (ref "U17") (pin "1") (pinfunction "VCC1_1") (pintype "power_in"))
      (node (ref "U21") (pin "1") (pinfunction "VCC1_1") (pintype "power_in"))
    )
    (net (code "2") (name "+5V_ALT") (class "Default")
      (node (ref "C26") (pin "1") (pinfunction "1_1") (pintype "passive"))
      (node (ref "C38") (pin "1") (pinfunction "1_1") (pintype "passive"))
      (node (ref "C49") (pin "1") (pinfunction "1_1") (pintype "passive"))
      (node (ref "C61") (pin "1") (pinfunction "1_1") (pintype "passive"))
      (node (ref "C71") (pin "1") (pinfunction "1_1") (pintype "passive"))
      (node (ref "C81") (pin "1") (pinfunction "1_1") (pintype "passive"))
      (node (ref "U15") (pin "1") (pinfunction "VCC1_1") (pintype "power_in"))
      (node (ref "U20") (pin "1") (pinfunction "VCC1_1") (pintype "power_in"))
      (node (ref "U9") (pin "1") (pinfunction "VCC1_1") (pintype "power_in"))
    )
    (net (code "3") (name "+12V") (class "Default")
      (node (ref "L1") (pin "1") (pinfunction "1_1") (pintype "passive"))
      (node (ref "L2") (pin "1") (pinfunction "1_1") (pintype "passive"))
      (node (ref "L3") (pin "1") (pinfunction "1_1") (pintype "passive"))
      (node (ref "L4") (pin "1") (pinfunction "1_1") (pintype "passive"))
      (node (ref "L5") (pin "1") (pinfunction "1_1") (pintype "passive"))
      (node (ref "L6") (pin "1") (pinfunction "1_1") (pintype "passive"))
    )
    (net (code "4") (name "/+15V_U_HS") (class "Default")
      (node (ref "C59") (pin "1") (pinfunction "1_1") (pintype "passive"))
      (node (ref "C67") (pin "1") (pinfunction "1_1") (pintype "passive"))
      (node (ref "U15") (pin "5") (pinfunction "VCC2_5") (pintype "power_in"))
      (node (ref "U18") (pin "7") (pinfunction "+VOUT_7") (pintype "passive"))
    )
    (net (code "5") (name "/+15V_U_LS") (class "Default")
      (node (ref "C79") (pin "1") (pinfunction "1_1") (pintype "passive"))
      (node (ref "C85") (pin "1") (pinfunction "1_1") (pintype "passive"))
      (node (ref "U20") (pin "5") (pinfunction "VCC2_5") (pintype "power_in"))
      (node (ref "U22") (pin "7") (pinfunction "+VOUT_7") (pintype "passive"))
    )
    (net (code "6") (name "/+15V_V_HS") (class "Default")
      (node (ref "C36") (pin "1") (pinfunction "1_1") (pintype "passive"))
      (node (ref "C42") (pin "1") (pinfunction "1_1") (pintype "passive"))
      (node (ref "U12") (pin "7") (pinfunction "+VOUT_7") (pintype "passive"))
      (node (ref "U9") (pin "5") (pinfunction "VCC2_5") (pintype "power_in"))
    )
    (net (code "7") (name "/+15V_V_LS") (class "Default")
      (node (ref "C74") (pin "1") (pinfunction "1_1") (pintype "passive"))
      (node (ref "C86") (pin "1") (pinfunction "1_1") (pintype "passive"))
      (node (ref "U21") (pin "5") (pinfunction "VCC2_5") (pintype "power_in"))
      (node (ref "U23") (pin "7") (pinfunction "+VOUT_7") (pintype "passive"))
    )
    (net (code "8") (name "/+15V_W_HS") (class "Default")
      (node (ref "C29") (pin "1") (pinfunction "1_1") (pintype "passive"))
      (node (ref "C43") (pin "1") (pinfunction "1_1") (pintype "passive"))
      (node (ref "U10") (pin "5") (pinfunction "VCC2_5") (pintype "power_in"))
      (node (ref "U13") (pin "7") (pinfunction "+VOUT_7") (pintype "passive"))
    )
    (net (code "9") (name "/+15V_W_LS") (class "Default")
      (node (ref "C52") (pin "1") (pinfunction "1_1") (pintype "passive"))
      (node (ref "C68") (pin "1") (pinfunction "1_1") (pintype "passive"))
      (node (ref "U17") (pin "5") (pinfunction "VCC2_5") (pintype "power_in"))
      (node (ref "U19") (pin "7") (pinfunction "+VOUT_7") (pintype "passive"))
    )
    (net (code "10") (name "/-3V_U_HS") (class "Default")
      (node (ref "C51") (pin "2") (pinfunction "2_2") (pintype "passive"))
      (node (ref "C65") (pin "2") (pinfunction "2_2") (pintype "passive"))
      (node (ref "U15") (pin "8") (pinfunction "VEE2_8") (pintype "power_in"))
      (node (ref "U18") (pin "5") (pinfunction "-VOUT_5") (pintype "passive"))
    )
    (net (code "11") (name "/-3V_U_LS") (class "Default")
      (node (ref "C73") (pin "2") (pinfunction "2_2") (pintype "passive"))
      (node (ref "C83") (pin "2") (pinfunction "2_2") (pintype "passive"))
      (node (ref "U20") (pin "8") (pinfunction "VEE2_8") (pintype "power_in"))
      (node (ref "U22") (pin "5") (pinfunction "-VOUT_5") (pintype "passive"))
    )
    (net (code "12") (name "/-3V_V_HS") (class "Default")
      (node (ref "C28") (pin "2") (pinfunction "2_2") (pintype "passive"))
      (node (ref "C40") (pin "2") (pinfunction "2_2") (pintype "passive"))
      (node (ref "U12") (pin "5") (pinfunction "-VOUT_5") (pintype "passive"))
      (node (ref "U9") (pin "8") (pinfunction "VEE2_8") (pintype "power_in"))
    )
    (net (code "13") (name "/-3V_V_LS") (class "Default")
      (node (ref "C80") (pin "2") (pinfunction "2_2") (pintype "passive"))
      (node (ref "C84") (pin "2") (pinfunction "2_2") (pintype "passive"))
      (node (ref "U21") (pin "8") (pinfunction "VEE2_8") (pintype "power_in"))
      (node (ref "U23") (pin "5") (pinfunction "-VOUT_5") (pintype "passive"))
    )
    (net (code "14") (name "/-3V_W_HS") (class "Default")
      (node (ref "C37") (pin "2") (pinfunction "2_2") (pintype "passive"))
      (node (ref "C41") (pin "2") (pinfunction "2_2") (pintype "passive"))
      (node (ref "U10") (pin "8") (pinfunction "VEE2_8") (pintype "power_in"))
      (node (ref "U13") (pin "5") (pinfunction "-VOUT_5") (pintype "passive"))
    )
    (net (code "15") (name "/-3V_W_LS") (class "Default")
      (node (ref "C60") (pin "2") (pinfunction "2_2") (pintype "passive"))
      (node (ref "C66") (pin "2") (pinfunction "2_2") (pintype "passive"))
      (node (ref "U17") (pin "8") (pinfunction "VEE2_8") (pintype "power_in"))
      (node (ref "U19") (pin "5") (pinfunction "-VOUT_5") (pintype "passive"))
    )
    (net (code "16") (name "/G1H") (class "Default")
      (node (ref "R105") (pin "1") (pinfunction "1_1") (pintype "passive"))
      (node (ref "U15") (pin "6") (pinfunction "OUTH_6") (pintype "output"))
    )
    (net (code "17") (name "/G1L") (class "Default")
      (node (ref "R97") (pin "1") (pinfunction "1_1") (pintype "passive"))
      (node (ref "U15") (pin "7") (pinfunction "OUTL_7") (pintype "input"))
    )
    (net (code "18") (name "/G2H") (class "Default")
      (node (ref "R131") (pin "1") (pinfunction "1_1") (pintype "passive"))
      (node (ref "U20") (pin "6") (pinfunction "OUTH_6") (pintype "output"))
    )
    (net (code "19") (name "/G2L") (class "Default")
      (node (ref "R123") (pin "1") (pinfunction "1_1") (pintype "passive"))
      (node (ref "U20") (pin "7") (pinfunction "OUTL_7") (pintype "input"))
    )
    (net (code "20") (name "/G3H") (class "Default")
      (node (ref "R74") (pin "1") (pinfunction "1_1") (pintype "passive"))
      (node (ref "U9") (pin "6") (pinfunction "OUTH_6") (pintype "output"))
    )
    (net (code "21") (name "/G3L") (class "Default")
      (node (ref "R67") (pin "1") (pinfunction "1_1") (pintype "passive"))
      (node (ref "U9") (pin "7") (pinfunction "OUTL_7") (pintype "input"))
    )
    (net (code "22") (name "/G4H") (class "Default")
      (node (ref "R124") (pin "1") (pinfunction "1_1") (pintype "passive"))
      (node (ref "U21") (pin "6") (pinfunction "OUTH_6") (pintype "output"))
    )
    (net (code "23") (name "/G4L") (class "Default")
      (node (ref "R132") (pin "1") (pinfunction "1_1") (pintype "passive"))
      (node (ref "U21") (pin "7") (pinfunction "OUTL_7") (pintype "input"))
    )
    (net (code "24") (name "/G5H") (class "Default")
      (node (ref "R68") (pin "1") (pinfunction "1_1") (pintype "passive"))
      (node (ref "U10") (pin "6") (pinfunction "OUTH_6") (pintype "output"))
    )
    (net (code "25") (name "/G5L") (class "Default")
      (node (ref "R75") (pin "1") (pinfunction "1_1") (pintype "passive"))
      (node (ref "U10") (pin "7") (pinfunction "OUTL_7") (pintype "input"))
    )
    (net (code "26") (name "/G6H") (class "Default")
      (node (ref "R98") (pin "1") (pinfunction "1_1") (pintype "passive"))
      (node (ref "U17") (pin "6") (pinfunction "OUTH_6") (pintype "output"))
    )
    (net (code "27") (name "/G6L") (class "Default")
      (node (ref "R106") (pin "1") (pinfunction "1_1") (pintype "passive"))
      (node (ref "U17") (pin "7") (pinfunction "OUTL_7") (pintype "input"))
    )
    (net (code "28") (name "/GD_DIS_FILT") (class "Default")
      (node (ref "C146") (pin "1") (pinfunction "1_1") (pintype "passive"))
      (node (ref "R220") (pin "2") (pinfunction "2_2") (pintype "passive"))
      (node (ref "R83") (pin "2") (pinfunction "2_2") (pintype "passive"))
      (node (ref "U11") (pin "1") (pinfunction "~{OE1}_1") (pintype "input"))
      (node (ref "U11") (pin "19") (pinfunction "~{OE2}_19") (pintype "input"))
    )
    (net (code "29") (name "/U_HS") (class "Default")
      (node (ref "R129") (pin "1") (pinfunction "1_1") (pintype "passive"))
      (node (ref "R214") (pin "2") (pinfunction "2_2") (pintype "passive"))
      (node (ref "R99") (pin "1") (pinfunction "1_1") (pintype "passive"))
      (node (ref "U11") (pin "14") (pinfunction "Y5_14") (pintype "tri_state"))
    )
    (net (code "30") (name "/U_HS+_FILT") (class "Default")
      (node (ref "C54") (pin "1") (pinfunction "1_1") (pintype "passive"))
      (node (ref "R99") (pin "2") (pinfunction "2_2") (pintype "passive"))
      (node (ref "U15") (pin "2") (pinfunction "IN+_2") (pintype "input"))
    )
    (net (code "31") (name "/U_HS-_FILT") (class "Default")
      (node (ref "C77") (pin "1") (pinfunction "1_1") (pintype "passive"))
      (node (ref "R129") (pin "2") (pinfunction "2_2") (pintype "passive"))
      (node (ref "U20") (pin "3") (pinfunction "IN-_3") (pintype "input"))
    )
    (net (code "32") (name "/U_LS") (class "Default")
      (node (ref "R103") (pin "1") (pinfunction "1_1") (pintype "passive"))
      (node (ref "R126") (pin "1") (pinfunction "1_1") (pintype "passive"))
      (node (ref "R216") (pin "2") (pinfunction "2_2") (pintype "passive"))
      (node (ref "U11") (pin "15") (pinfunction "Y4_15") (pintype "tri_state"))
    )
    (net (code "33") (name "/U_LS+_FILT") (class "Default")
      (node (ref "C75") (pin "1") (pinfunction "1_1") (pintype "passive"))
      (node (ref "R126") (pin "2") (pinfunction "2_2") (pintype "passive"))
      (node (ref "U20") (pin "2") (pinfunction "IN+_2") (pintype "input"))
    )
    (net (code "34") (name "/U_LS-_FILT") (class "Default")
      (node (ref "C57") (pin "1") (pinfunction "1_1") (pintype "passive"))
      (node (ref "R103") (pin "2") (pinfunction "2_2") (pintype "passive"))
      (node (ref "U15") (pin "3") (pinfunction "IN-_3") (pintype "input"))
    )
    (net (code "35") (name "/V_HS") (class "Default")
      (node (ref "R127") (pin "1") (pinfunction "1_1") (pintype "passive"))
      (node (ref "R218") (pin "2") (pinfunction "2_2") (pintype "passive"))
      (node (ref "R69") (pin "1") (pinfunction "1_1") (pintype "passive"))
      (node (ref "U11") (pin "17") (pinfunction "Y2_17") (pintype "tri_state"))
    )
    (net (code "36") (name "/V_HS+_FILT") (class "Default")
      (node (ref "C32") (pin "1") (pinfunction "1_1") (pintype "passive"))
      (node (ref "R69") (pin "2") (pinfunction "2_2") (pintype "passive"))
      (node (ref "U9") (pin "2") (pinfunction "IN+_2") (pintype "input"))
    )
    (net (code "37") (name "/V_HS-_FILT") (class "Default")
      (node (ref "C76") (pin "1") (pinfunction "1_1") (pintype "passive"))
      (node (ref "R127") (pin "2") (pinfunction "2_2") (pintype "passive"))
      (node (ref "U21") (pin "3") (pinfunction "IN-_3") (pintype "input"))
    )
    (net (code "38") (name "/V_LS") (class "Default")
      (node (ref "R130") (pin "1") (pinfunction "1_1") (pintype "passive"))
      (node (ref "R219") (pin "2") (pinfunction "2_2") (pintype "passive"))
      (node (ref "R72") (pin "1") (pinfunction "1_1") (pintype "passive"))
      (node (ref "U11") (pin "18") (pinfunction "Y1_18") (pintype "tri_state"))
    )
    (net (code "39") (name "/V_LS+_FILT") (class "Default")
      (node (ref "C78") (pin "1") (pinfunction "1_1") (pintype "passive"))
      (node (ref "R130") (pin "2") (pinfunction "2_2") (pintype "passive"))
      (node (ref "U21") (pin "2") (pinfunction "IN+_2") (pintype "input"))
    )
    (net (code "40") (name "/V_LS-_FILT") (class "Default")
      (node (ref "C34") (pin "1") (pinfunction "1_1") (pintype "passive"))
      (node (ref "R72") (pin "2") (pinfunction "2_2") (pintype "passive"))
      (node (ref "U9") (pin "3") (pinfunction "IN-_3") (pintype "input"))
    )
    (net (code "41") (name "/W_HS") (class "Default")
      (node (ref "R100") (pin "1") (pinfunction "1_1") (pintype "passive"))
      (node (ref "R215") (pin "2") (pinfunction "2_2") (pintype "passive"))
      (node (ref "R73") (pin "1") (pinfunction "1_1") (pintype "passive"))
      (node (ref "U11") (pin "11") (pinfunction "Y8_11") (pintype "tri_state"))
    )
    (net (code "42") (name "/W_HS+_FILT") (class "Default")
      (node (ref "C35") (pin "1") (pinfunction "1_1") (pintype "passive"))
      (node (ref "R73") (pin "2") (pinfunction "2_2") (pintype "passive"))
      (node (ref "U10") (pin "2") (pinfunction "IN+_2") (pintype "input"))
    )
    (net (code "43") (name "/W_HS-_FILT") (class "Default")
      (node (ref "C55") (pin "1") (pinfunction "1_1") (pintype "passive"))
      (node (ref "R100") (pin "2") (pinfunction "2_2") (pintype "passive"))
      (node (ref "U17") (pin "3") (pinfunction "IN-_3") (pintype "input"))
    )
    (net (code "44") (name "/W_LS") (class "Default")
      (node (ref "R104") (pin "1") (pinfunction "1_1") (pintype "passive"))
      (node (ref "R217") (pin "2") (pinfunction "2_2") (pintype "passive"))
      (node (ref "R70") (pin "1") (pinfunction "1_1") (pintype "passive"))
      (node (ref "U11") (pin "12") (pinfunction "Y7_12") (pintype "tri_state"))
    )
    (net (code "45") (name "/W_LS+_FILT") (class "Default")
      (node (ref "C58") (pin "1") (pinfunction "1_1") (pintype "passive"))
      (node (ref "R104") (pin "2") (pinfunction "2_2") (pintype "passive"))
      (node (ref "U17") (pin "2") (pinfunction "IN+_2") (pintype "input"))
    )
    (net (code "46") (name "/W_LS-_FILT") (class "Default")
      (node (ref "C33") (pin "1") (pinfunction "1_1") (pintype "passive"))
      (node (ref "R70") (pin "2") (pinfunction "2_2") (pintype "passive"))
      (node (ref "U10") (pin "3") (pinfunction "IN-_3") (pintype "input"))
    )
    (net (code "47") (name "G1") (class "Default")
      (node (ref "R105") (pin "2") (pinfunction "2_2") (pintype "passive"))
      (node (ref "R94") (pin "2") (pinfunction "2_2") (pintype "passive"))
      (node (ref "R97") (pin "2") (pinfunction "2_2") (pintype "passive"))
    )
    (net (code "48") (name "G2") (class "Default")
      (node (ref "R120") (pin "2") (pinfunction "2_2") (pintype "passive"))
      (node (ref "R123") (pin "2") (pinfunction "2_2") (pintype "passive"))
      (node (ref "R131") (pin "2") (pinfunction "2_2") (pintype "passive"))
    )
    (net (code "49") (name "G3") (class "Default")
      (node (ref "R64") (pin "2") (pinfunction "2_2") (pintype "passive"))
      (node (ref "R67") (pin "2") (pinfunction "2_2") (pintype "passive"))
      (node (ref "R74") (pin "2") (pinfunction "2_2") (pintype "passive"))
    )
    (net (code "50") (name "G4") (class "Default")
      (node (ref "R121") (pin "2") (pinfunction "2_2") (pintype "passive"))
      (node (ref "R124") (pin "2") (pinfunction "2_2") (pintype "passive"))
      (node (ref "R132") (pin "2") (pinfunction "2_2") (pintype "passive"))
    )
    (net (code "51") (name "G5") (class "Default")
      (node (ref "R65") (pin "2") (pinfunction "2_2") (pintype "passive"))
      (node (ref "R68") (pin "2") (pinfunction "2_2") (pintype "passive"))
      (node (ref "R75") (pin "2") (pinfunction "2_2") (pintype "passive"))
    )
    (net (code "52") (name "G6") (class "Default")
      (node (ref "R106") (pin "2") (pinfunction "2_2") (pintype "passive"))
      (node (ref "R95") (pin "2") (pinfunction "2_2") (pintype "passive"))
      (node (ref "R98") (pin "2") (pinfunction "2_2") (pintype "passive"))
    )
    (net (code "53") (name "GD_DIS") (class "Default")
      (node (ref "R83") (pin "1") (pinfunction "1_1") (pintype "passive"))
    )
    (net (code "54") (name "GND") (class "Default")
      (node (ref "C146") (pin "2") (pinfunction "2_2") (pintype "passive"))
      (node (ref "C147") (pin "2") (pinfunction "2_2") (pintype "passive"))
      (node (ref "C26") (pin "2") (pinfunction "2_2") (pintype "passive"))
      (node (ref "C27") (pin "2") (pinfunction "2_2") (pintype "passive"))
      (node (ref "C32") (pin "2") (pinfunction "2_2") (pintype "passive"))
      (node (ref "C33") (pin "2") (pinfunction "2_2") (pintype "passive"))
      (node (ref "C34") (pin "2") (pinfunction "2_2") (pintype "passive"))
      (node (ref "C35") (pin "2") (pinfunction "2_2") (pintype "passive"))
      (node (ref "C38") (pin "2") (pinfunction "2_2") (pintype "passive"))
      (node (ref "C39") (pin "2") (pinfunction "2_2") (pintype "passive"))
      (node (ref "C49") (pin "2") (pinfunction "2_2") (pintype "passive"))
      (node (ref "C50") (pin "2") (pinfunction "2_2") (pintype "passive"))
      (node (ref "C54") (pin "2") (pinfunction "2_2") (pintype "passive"))
      (node (ref "C55") (pin "2") (pinfunction "2_2") (pintype "passive"))
      (node (ref "C57") (pin "2") (pinfunction "2_2") (pintype "passive"))
      (node (ref "C58") (pin "2") (pinfunction "2_2") (pintype "passive"))
      (node (ref "C61") (pin "2") (pinfunction "2_2") (pintype "passive"))
      (node (ref "C62") (pin "2") (pinfunction "2_2") (pintype "passive"))
      (node (ref "C71") (pin "2") (pinfunction "2_2") (pintype "passive"))
      (node (ref "C72") (pin "2") (pinfunction "2_2") (pintype "passive"))
      (node (ref "C75") (pin "2") (pinfunction "2_2") (pintype "passive"))
      (node (ref "C76") (pin "2") (pinfunction "2_2") (pintype "passive"))
      (node (ref "C77") (pin "2") (pinfunction "2_2") (pintype "passive"))
      (node (ref "C78") (pin "2") (pinfunction "2_2") (pintype "passive"))
      (node (ref "C81") (pin "2") (pinfunction "2_2") (pintype "passive"))
      (node (ref "C82") (pin "2") (pinfunction "2_2") (pintype "passive"))
      (node (ref "L1") (pin "2") (pinfunction "2_2") (pintype "passive"))
      (node (ref "L2") (pin "2") (pinfunction "2_2") (pintype "passive"))
      (node (ref "L3") (pin "2") (pinfunction "2_2") (pintype "passive"))
      (node (ref "L4") (pin "2") (pinfunction "2_2") (pintype "passive"))
      (node (ref "L5") (pin "2") (pinfunction "2_2") (pintype "passive"))
      (node (ref "L6") (pin "2") (pinfunction "2_2") (pintype "passive"))
      (node (ref "R214") (pin "1") (pinfunction "1_1") (pintype "passive"))
      (node (ref "R215") (pin "1") (pinfunction "1_1") (pintype "passive"))
      (node (ref "R216") (pin "1") (pinfunction "1_1") (pintype "passive"))
      (node (ref "R217") (pin "1") (pinfunction "1_1") (pintype "passive"))
      (node (ref "R218") (pin "1") (pinfunction "1_1") (pintype "passive"))
      (node (ref "R219") (pin "1") (pinfunction "1_1") (pintype "passive"))
      (node (ref "R220") (pin "1") (pinfunction "1_1") (pintype "passive"))
      (node (ref "U10") (pin "4") (pinfunction "GND1_4") (pintype "power_in"))
      (node (ref "U11") (pin "10") (pinfunction "GND_10") (pintype "power_in"))
      (node (ref "U11") (pin "4") (pinfunction "A3_4") (pintype "input"))
      (node (ref "U11") (pin "7") (pinfunction "A6_7") (pintype "input"))
      (node (ref "U15") (pin "4") (pinfunction "GND1_4") (pintype "power_in"))
      (node (ref "U17") (pin "4") (pinfunction "GND1_4") (pintype "power_in"))
      (node (ref "U20") (pin "4") (pinfunction "GND1_4") (pintype "power_in"))
      (node (ref "U21") (pin "4") (pinfunction "GND1_4") (pintype "power_in"))
      (node (ref "U9") (pin "4") (pinfunction "GND1_4") (pintype "power_in"))
    )
    (net (code "55") (name "Net-(U12-+VIN)") (class "Default")
      (node (ref "C47") (pin "1") (pinfunction "1_1") (pintype "passive"))
      (node (ref "L1") (pin "4") (pinfunction "4_4") (pintype "passive"))
      (node (ref "U12") (pin "1") (pinfunction "+VIN_1") (pintype "passive"))
    )
    (net (code "56") (name "Net-(U12--VIN)") (class "Default")
      (node (ref "C47") (pin "2") (pinfunction "2_2") (pintype "passive"))
      (node (ref "L1") (pin "3") (pinfunction "3_3") (pintype "passive"))
      (node (ref "U12") (pin "2") (pinfunction "-VIN_2") (pintype "passive"))
    )
    (net (code "57") (name "Net-(U13-+VIN)") (class "Default")
      (node (ref "C48") (pin "1") (pinfunction "1_1") (pintype "passive"))
      (node (ref "L2") (pin "4") (pinfunction "4_4") (pintype "passive"))
      (node (ref "U13") (pin "1") (pinfunction "+VIN_1") (pintype "passive"))
    )
    (net (code "58") (name "Net-(U13--VIN)") (class "Default")
      (node (ref "C48") (pin "2") (pinfunction "2_2") (pintype "passive"))
      (node (ref "L2") (pin "3") (pinfunction "3_3") (pintype "passive"))
      (node (ref "U13") (pin "2") (pinfunction "-VIN_2") (pintype "passive"))
    )
    (net (code "59") (name "Net-(U18-+VIN)") (class "Default")
      (node (ref "C69") (pin "1") (pinfunction "1_1") (pintype "passive"))
      (node (ref "L3") (pin "4") (pinfunction "4_4") (pintype "passive"))
      (node (ref "U18") (pin "1") (pinfunction "+VIN_1") (pintype "passive"))
    )
    (net (code "60") (name "Net-(U18--VIN)") (class "Default")
      (node (ref "C69") (pin "2") (pinfunction "2_2") (pintype "passive"))
      (node (ref "L3") (pin "3") (pinfunction "3_3") (pintype "passive"))
      (node (ref "U18") (pin "2") (pinfunction "-VIN_2") (pintype "passive"))
    )
    (net (code "61") (name "Net-(U19-+VIN)") (class "Default")
      (node (ref "C70") (pin "1") (pinfunction "1_1") (pintype "passive"))
      (node (ref "L4") (pin "4") (pinfunction "4_4") (pintype "passive"))
      (node (ref "U19") (pin "1") (pinfunction "+VIN_1") (pintype "passive"))
    )
    (net (code "62") (name "Net-(U19--VIN)") (class "Default")
      (node (ref "C70") (pin "2") (pinfunction "2_2") (pintype "passive"))
      (node (ref "L4") (pin "3") (pinfunction "3_3") (pintype "passive"))
      (node (ref "U19") (pin "2") (pinfunction "-VIN_2") (pintype "passive"))
    )
    (net (code "63") (name "Net-(U22-+VIN)") (class "Default")
      (node (ref "C87") (pin "1") (pinfunction "1_1") (pintype "passive"))
      (node (ref "L5") (pin "4") (pinfunction "4_4") (pintype "passive"))
      (node (ref "U22") (pin "1") (pinfunction "+VIN_1") (pintype "passive"))
    )
    (net (code "64") (name "Net-(U22--VIN)") (class "Default")
      (node (ref "C87") (pin "2") (pinfunction "2_2") (pintype "passive"))
      (node (ref "L5") (pin "3") (pinfunction "3_3") (pintype "passive"))
      (node (ref "U22") (pin "2") (pinfunction "-VIN_2") (pintype "passive"))
    )
    (net (code "65") (name "Net-(U23-+VIN)") (class "Default")
      (node (ref "C88") (pin "1") (pinfunction "1_1") (pintype "passive"))
      (node (ref "L6") (pin "4") (pinfunction "4_4") (pintype "passive"))
      (node (ref "U23") (pin "1") (pinfunction "+VIN_1") (pintype "passive"))
    )
    (net (code "66") (name "Net-(U23--VIN)") (class "Default")
      (node (ref "C88") (pin "2") (pinfunction "2_2") (pintype "passive"))
      (node (ref "L6") (pin "3") (pinfunction "3_3") (pintype "passive"))
      (node (ref "U23") (pin "2") (pinfunction "-VIN_2") (pintype "passive"))
    )
    (net (code "67") (name "S1") (class "Default")
      (node (ref "C51") (pin "1") (pinfunction "1_1") (pintype "passive"))
      (node (ref "C59") (pin "2") (pinfunction "2_2") (pintype "passive"))
      (node (ref "C65") (pin "1") (pinfunction "1_1") (pintype "passive"))
      (node (ref "C67") (pin "2") (pinfunction "2_2") (pintype "passive"))
      (node (ref "R94") (pin "1") (pinfunction "1_1") (pintype "passive"))
      (node (ref "U18") (pin "6") (pinfunction "0V_6") (pintype "passive"))
    )
    (net (code "68") (name "S2") (class "Default")
      (node (ref "C73") (pin "1") (pinfunction "1_1") (pintype "passive"))
      (node (ref "C79") (pin "2") (pinfunction "2_2") (pintype "passive"))
      (node (ref "C83") (pin "1") (pinfunction "1_1") (pintype "passive"))
      (node (ref "C85") (pin "2") (pinfunction "2_2") (pintype "passive"))
      (node (ref "R120") (pin "1") (pinfunction "1_1") (pintype "passive"))
      (node (ref "U22") (pin "6") (pinfunction "0V_6") (pintype "passive"))
    )
    (net (code "69") (name "S3") (class "Default")
      (node (ref "C28") (pin "1") (pinfunction "1_1") (pintype "passive"))
      (node (ref "C36") (pin "2") (pinfunction "2_2") (pintype "passive"))
      (node (ref "C40") (pin "1") (pinfunction "1_1") (pintype "passive"))
      (node (ref "C42") (pin "2") (pinfunction "2_2") (pintype "passive"))
      (node (ref "R64") (pin "1") (pinfunction "1_1") (pintype "passive"))
      (node (ref "U12") (pin "6") (pinfunction "0V_6") (pintype "passive"))
    )
    (net (code "70") (name "S4") (class "Default")
      (node (ref "C74") (pin "2") (pinfunction "2_2") (pintype "passive"))
      (node (ref "C80") (pin "1") (pinfunction "1_1") (pintype "passive"))
      (node (ref "C84") (pin "1") (pinfunction "1_1") (pintype "passive"))
      (node (ref "C86") (pin "2") (pinfunction "2_2") (pintype "passive"))
      (node (ref "R121") (pin "1") (pinfunction "1_1") (pintype "passive"))
      (node (ref "U23") (pin "6") (pinfunction "0V_6") (pintype "passive"))
    )
    (net (code "71") (name "S5") (class "Default")
      (node (ref "C29") (pin "2") (pinfunction "2_2") (pintype "passive"))
      (node (ref "C37") (pin "1") (pinfunction "1_1") (pintype "passive"))
      (node (ref "C41") (pin "1") (pinfunction "1_1") (pintype "passive"))
      (node (ref "C43") (pin "2") (pinfunction "2_2") (pintype "passive"))
      (node (ref "R65") (pin "1") (pinfunction "1_1") (pintype "passive"))
      (node (ref "U13") (pin "6") (pinfunction "0V_6") (pintype "passive"))
    )
    (net (code "72") (name "S6") (class "Default")
      (node (ref "C52") (pin "2") (pinfunction "2_2") (pintype "passive"))
      (node (ref "C60") (pin "1") (pinfunction "1_1") (pintype "passive"))
      (node (ref "C66") (pin "1") (pinfunction "1_1") (pintype "passive"))
      (node (ref "C68") (pin "2") (pinfunction "2_2") (pintype "passive"))
      (node (ref "R95") (pin "1") (pinfunction "1_1") (pintype "passive"))
      (node (ref "U19") (pin "6") (pinfunction "0V_6") (pintype "passive"))
    )
    (net (code "73") (name "U_HS_PWM") (class "Default")
      (node (ref "U11") (pin "6") (pinfunction "A5_6") (pintype "input"))
    )
    (net (code "74") (name "U_LS_PWM") (class "Default")
      (node (ref "U11") (pin "5") (pinfunction "A4_5") (pintype "input"))
    )
    (net (code "75") (name "V_HS_PWM") (class "Default")
      (node (ref "U11") (pin "3") (pinfunction "A2_3") (pintype "input"))
    )
    (net (code "76") (name "V_LS_PWM") (class "Default")
      (node (ref "U11") (pin "2") (pinfunction "A1_2") (pintype "input"))
    )
    (net (code "77") (name "W_HS_PWM") (class "Default")
      (node (ref "U11") (pin "9") (pinfunction "A8_9") (pintype "input"))
    )
    (net (code "78") (name "W_LS_PWM") (class "Default")
      (node (ref "U11") (pin "8") (pinfunction "A7_8") (pintype "input"))
    )
    (net (code "79") (name "unconnected-(U11-Y3-Pad16)") (class "Default")
      (node (ref "U11") (pin "16") (pinfunction "Y3_16") (pintype "tri_state"))
    )
    (net (code "80") (name "unconnected-(U11-Y6-Pad13)") (class "Default")
      (node (ref "U11") (pin "13") (pinfunction "Y6_13") (pintype "tri_state"))
    )
  )
)
